# ADC_Module.net
KiCad netlist of a schematic drawn in Altium Designer
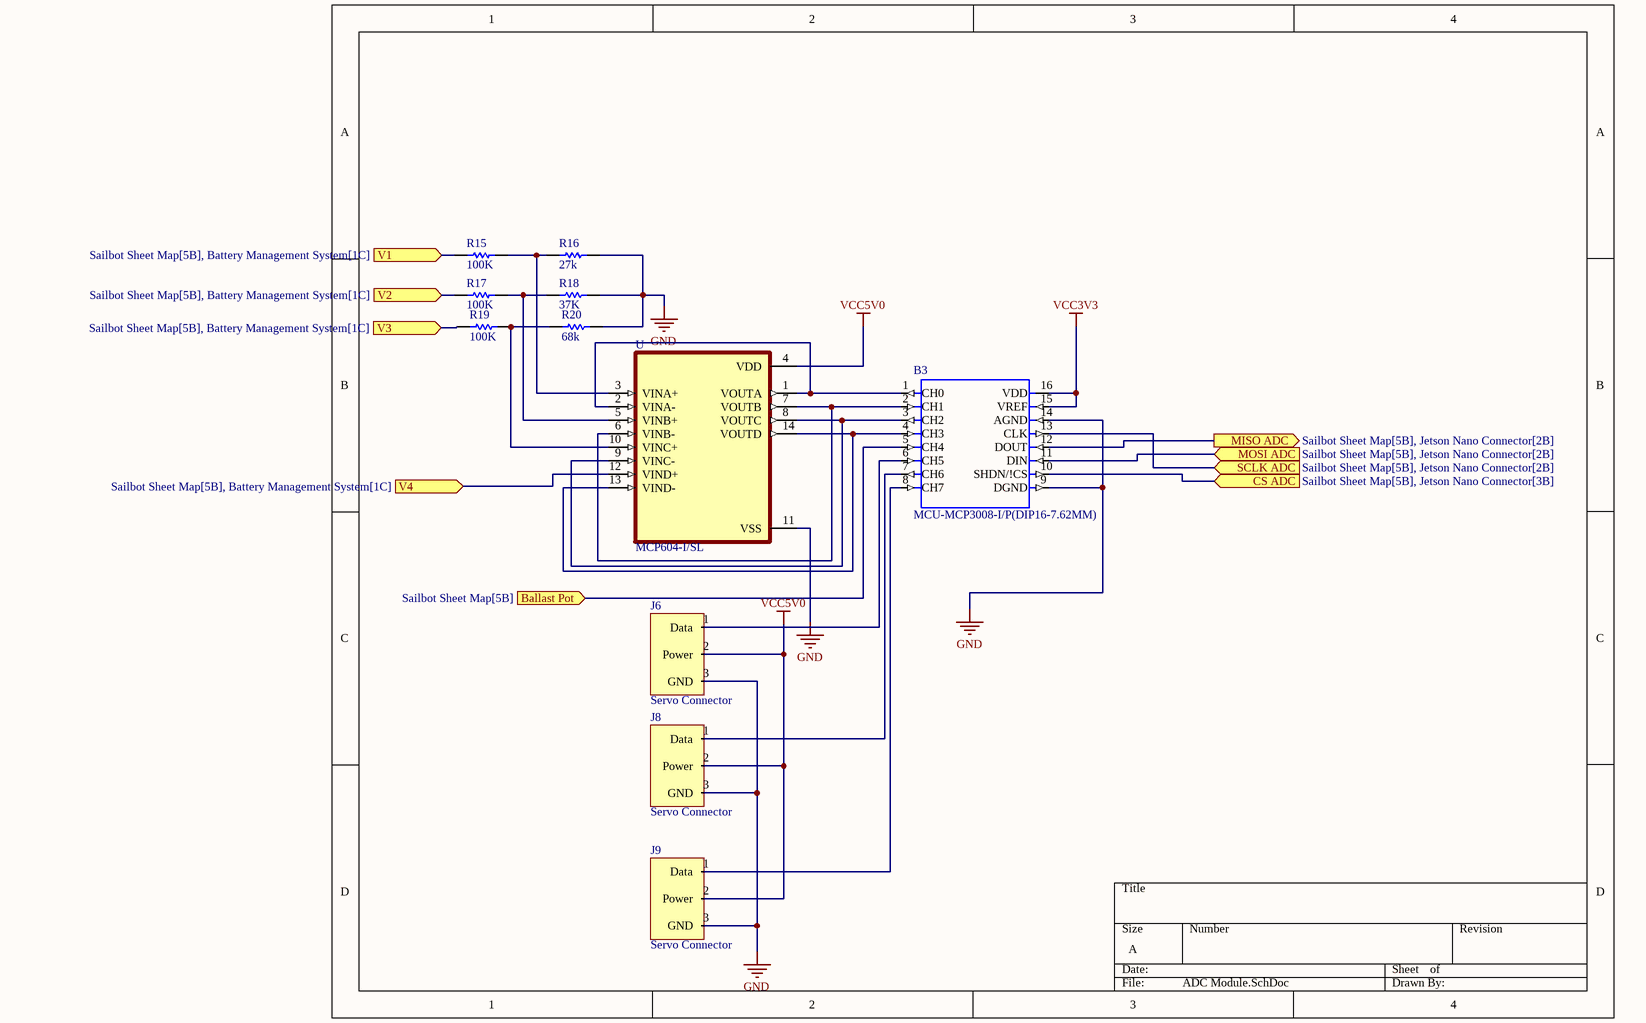
[diagram p0: ADC Module.SchDoc]

(export (version "E")
  (design (tool "Eeschema 10.0.6"))
  (components
    (comp (ref "B3")
      (value "MCU-MCP3008-I/P(DIP16-7.62MM)")
      (footprint "DIP16-2.54-19.2X7.62MM")
      (description "10 Bit Analog to Digital Converter 4, 8 Input 1 SAR 16-PDIP")
      (fields (field (name "MP") "MCP3008-I/P") (field (name "MF") "Microchip"))
      (libsource (lib "Sailbot Library") (part "MCU-MCP3008-I/P(DIP16-7.62MM)"))
    )
    (comp (ref "J6")
      (value "Servo Connector")
      (footprint "3 Pin 0.1in Header")
      (libsource (lib "Sailbot Library") (part "Servo Connector"))
    )
    (comp (ref "J8")
      (value "Servo Connector")
      (footprint "3 Pin 0.1in Header")
      (libsource (lib "Sailbot Library") (part "Servo Connector"))
    )
    (comp (ref "J9")
      (value "Servo Connector")
      (footprint "3 Pin 0.1in Header")
      (libsource (lib "Sailbot Library") (part "Servo Connector"))
    )
    (comp (ref "R15")
      (value "100K")
      (footprint "6-0805_M")
      (description "Resistor")
      (libsource (lib "Simulation Generic Components") (part "Resistor"))
    )
    (comp (ref "R16")
      (value "27k")
      (footprint "6-0805_M")
      (description "Resistor")
      (libsource (lib "Simulation Generic Components") (part "Resistor"))
    )
    (comp (ref "R17")
      (value "100K")
      (footprint "6-0805_M")
      (description "Resistor")
      (libsource (lib "Simulation Generic Components") (part "Resistor"))
    )
    (comp (ref "R18")
      (value "37K")
      (footprint "6-0805_M")
      (description "Resistor")
      (libsource (lib "Simulation Generic Components") (part "Resistor"))
    )
    (comp (ref "R19")
      (value "100K")
      (footprint "6-0805_M")
      (description "Resistor")
      (libsource (lib "Simulation Generic Components") (part "Resistor"))
    )
    (comp (ref "R20")
      (value "68k")
      (footprint "6-0805_M")
      (description "Resistor")
      (libsource (lib "Simulation Generic Components") (part "Resistor"))
    )
    (comp (ref "U")
      (value "MCP604-I/SL")
      (footprint "SOIC127P600X175-14N")
      (description "General Purpose Amplifier 4 Circuit Rail-to-Rail 14-SOIC")
      (fields (field (name "MF") "Microchip"))
      (libsource (lib "Sailbot Library") (part "MCP604-I/SL"))
    )
  )
  (nets
    (net (code "1") (name "/Ballast Pot") (class "Default")
      (node (ref "B3") (pin "5") (pinfunction "CH4_5") (pintype "input"))
    )
    (net (code "2") (name "/CS ADC") (class "Default")
      (node (ref "B3") (pin "10") (pinfunction "SHDN/!CS_10") (pintype "output"))
    )
    (net (code "3") (name "/MISO ADC") (class "Default")
      (node (ref "B3") (pin "12") (pinfunction "DOUT_12") (pintype "input"))
    )
    (net (code "4") (name "/MOSI ADC") (class "Default")
      (node (ref "B3") (pin "11") (pinfunction "DIN_11") (pintype "input"))
    )
    (net (code "5") (name "/SCLK ADC") (class "Default")
      (node (ref "B3") (pin "13") (pinfunction "CLK_13") (pintype "output"))
    )
    (net (code "6") (name "/V1") (class "Default")
      (node (ref "R15") (pin "2") (pinfunction "2_2") (pintype "passive"))
    )
    (net (code "7") (name "/V2") (class "Default")
      (node (ref "R17") (pin "2") (pinfunction "2_2") (pintype "passive"))
    )
    (net (code "8") (name "/V3") (class "Default")
      (node (ref "R19") (pin "2") (pinfunction "2_2") (pintype "passive"))
    )
    (net (code "9") (name "/V4") (class "Default")
      (node (ref "U") (pin "12") (pinfunction "VIND+_12") (pintype "input"))
    )
    (net (code "10") (name "GND") (class "Default")
      (node (ref "B3") (pin "14") (pinfunction "AGND_14") (pintype "input"))
      (node (ref "B3") (pin "9") (pinfunction "DGND_9") (pintype "output"))
      (node (ref "J6") (pin "3") (pinfunction "GND_3") (pintype "passive"))
      (node (ref "J8") (pin "3") (pinfunction "GND_3") (pintype "passive"))
      (node (ref "J9") (pin "3") (pinfunction "GND_3") (pintype "passive"))
      (node (ref "R16") (pin "1") (pinfunction "1_1") (pintype "passive"))
      (node (ref "R18") (pin "1") (pinfunction "1_1") (pintype "passive"))
      (node (ref "R20") (pin "2") (pinfunction "2_2") (pintype "passive"))
      (node (ref "U") (pin "11") (pinfunction "VSS_11") (pintype "power_in"))
    )
    (net (code "11") (name "Net-(B3-CH0)") (class "Default")
      (node (ref "B3") (pin "1") (pinfunction "CH0_1") (pintype "output"))
      (node (ref "U") (pin "1") (pinfunction "VOUTA_1") (pintype "output"))
      (node (ref "U") (pin "2") (pinfunction "VINA-_2") (pintype "input"))
    )
    (net (code "12") (name "Net-(B3-CH1)") (class "Default")
      (node (ref "B3") (pin "2") (pinfunction "CH1_2") (pintype "input"))
      (node (ref "U") (pin "6") (pinfunction "VINB-_6") (pintype "input"))
      (node (ref "U") (pin "7") (pinfunction "VOUTB_7") (pintype "output"))
    )
    (net (code "13") (name "Net-(B3-CH2)") (class "Default")
      (node (ref "B3") (pin "3") (pinfunction "CH2_3") (pintype "output"))
      (node (ref "U") (pin "8") (pinfunction "VOUTC_8") (pintype "output"))
      (node (ref "U") (pin "9") (pinfunction "VINC-_9") (pintype "input"))
    )
    (net (code "14") (name "Net-(B3-CH3)") (class "Default")
      (node (ref "B3") (pin "4") (pinfunction "CH3_4") (pintype "input"))
      (node (ref "U") (pin "13") (pinfunction "VIND-_13") (pintype "input"))
      (node (ref "U") (pin "14") (pinfunction "VOUTD_14") (pintype "output"))
    )
    (net (code "15") (name "Net-(B3-CH5)") (class "Default")
      (node (ref "B3") (pin "6") (pinfunction "CH5_6") (pintype "input"))
      (node (ref "J6") (pin "1") (pinfunction "Data_1") (pintype "passive"))
    )
    (net (code "16") (name "Net-(B3-CH6)") (class "Default")
      (node (ref "B3") (pin "7") (pinfunction "CH6_7") (pintype "output"))
      (node (ref "J8") (pin "1") (pinfunction "Data_1") (pintype "passive"))
    )
    (net (code "17") (name "Net-(B3-CH7)") (class "Default")
      (node (ref "B3") (pin "8") (pinfunction "CH7_8") (pintype "input"))
      (node (ref "J9") (pin "1") (pinfunction "Data_1") (pintype "passive"))
    )
    (net (code "18") (name "Net-(U-VINA+)") (class "Default")
      (node (ref "R15") (pin "1") (pinfunction "1_1") (pintype "passive"))
      (node (ref "R16") (pin "2") (pinfunction "2_2") (pintype "passive"))
      (node (ref "U") (pin "3") (pinfunction "VINA+_3") (pintype "input"))
    )
    (net (code "19") (name "Net-(U-VINB+)") (class "Default")
      (node (ref "R17") (pin "1") (pinfunction "1_1") (pintype "passive"))
      (node (ref "R18") (pin "2") (pinfunction "2_2") (pintype "passive"))
      (node (ref "U") (pin "5") (pinfunction "VINB+_5") (pintype "input"))
    )
    (net (code "20") (name "Net-(U-VINC+)") (class "Default")
      (node (ref "R19") (pin "1") (pinfunction "1_1") (pintype "passive"))
      (node (ref "R20") (pin "1") (pinfunction "1_1") (pintype "passive"))
      (node (ref "U") (pin "10") (pinfunction "VINC+_10") (pintype "input"))
    )
    (net (code "21") (name "VCC3V3") (class "Default")
      (node (ref "B3") (pin "15") (pinfunction "VREF_15") (pintype "input"))
      (node (ref "B3") (pin "16") (pinfunction "VDD_16") (pintype "power_in"))
    )
    (net (code "22") (name "VCC5V0") (class "Default")
      (node (ref "J6") (pin "2") (pinfunction "Power_2") (pintype "passive"))
      (node (ref "J8") (pin "2") (pinfunction "Power_2") (pintype "passive"))
      (node (ref "J9") (pin "2") (pinfunction "Power_2") (pintype "passive"))
      (node (ref "U") (pin "4") (pinfunction "VDD_4") (pintype "power_in"))
    )
  )
)
